# PCB_Switch.net
KiCad netlist of a schematic drawn in Altium Designer
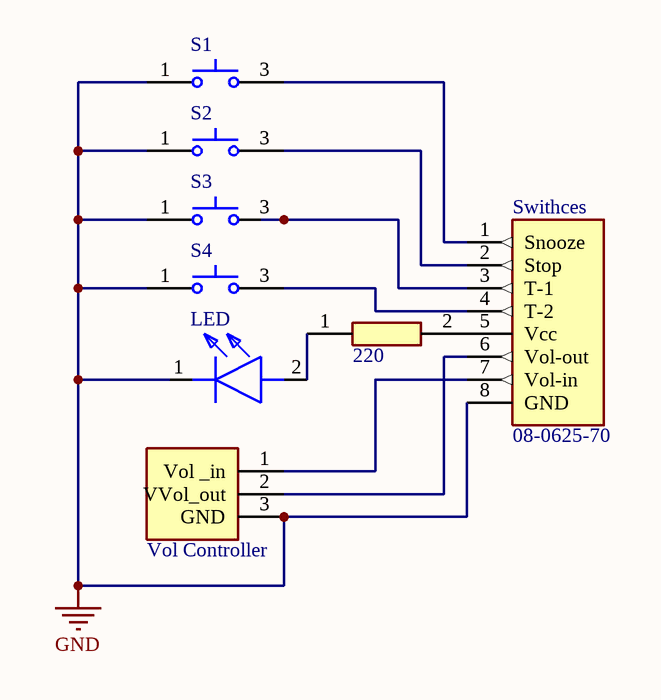
[diagram p0: PCB_Switch.SchDoc]

(export (version "E")
  (design (tool "Eeschema 10.0.6"))
  (components
    (comp (ref "LED")
      (value "SSL-LX5093TC")
      (footprint "SamacSys:SSL-LX5093SGC/B")
      (description "LED")
      (fields (field (name "MOUSER PART NUMBER") "696-SSL-LX5093TC"))
      (libsource (lib "*") (part "SSL-LX5093TC"))
    )
    (comp (ref "R")
      (value "220")
      (footprint "SamacSys:RESAD2400W59L1000D350")
      (description "Resistor")
      (fields (field (name "MANUFACTURER_PART_NUMBER") "293-220-RC"))
      (libsource (lib "*") (part "293-220-RC"))
    )
    (comp (ref "S1")
      (value "EP11SD1CBE")
      (footprint "SamacSys:EP11SD1CBE")
      (description "Switch (2-Pin Push)")
      (fields (field (name "MOUSER PART NUMBER") "611-EP11-003"))
      (libsource (lib "*") (part "EP11SD1CBE"))
    )
    (comp (ref "S2")
      (value "EP11SD1CBE")
      (footprint "SamacSys:EP11SD1CBE")
      (description "Switch (2-Pin Push)")
      (fields (field (name "MOUSER PART NUMBER") "611-EP11-003"))
      (libsource (lib "*") (part "EP11SD1CBE"))
    )
    (comp (ref "S3")
      (value "EP11SD1CBE")
      (footprint "SamacSys:EP11SD1CBE")
      (description "Switch (2-Pin Push)")
      (fields (field (name "MOUSER PART NUMBER") "611-EP11-003"))
      (libsource (lib "*") (part "EP11SD1CBE"))
    )
    (comp (ref "S4")
      (value "EP11SD1CBE")
      (footprint "SamacSys:EP11SD1CBE")
      (description "Switch (2-Pin Push)")
      (fields (field (name "MOUSER PART NUMBER") "611-EP11-003"))
      (libsource (lib "*") (part "EP11SD1CBE"))
    )
    (comp (ref "Swithces")
      (value "08-0625-70")
      (footprint "SamacSys:HDRV8W51P0X254_1X8_2032X254X816P")
      (description "Connector")
      (fields (field (name "MOUSER PART NUMBER") "535-08-0625-70"))
      (libsource (lib "*") (part "08-0625-70"))
    )
    (comp (ref "Vol Controller")
      (value "14910A0BHSX10502KA")
      (footprint "SamacSys:14910F0GJSX10103KA")
      (description "Variable Resistor")
      (fields (field (name "MOUSER PART NUMBER") "594-14910A0BHSP502KA"))
      (libsource (lib "*") (part "14910A0BHSX10502KA"))
    )
  )
  (nets
    (net (code "1") (name "GND") (class "Default")
      (node (ref "LED") (pin "1") (pinfunction "K_1") (pintype "passive"))
      (node (ref "S1") (pin "1") (pinfunction "NO_1_1") (pintype "passive"))
      (node (ref "S2") (pin "1") (pinfunction "NO_1_1") (pintype "passive"))
      (node (ref "S3") (pin "1") (pinfunction "NO_1_1") (pintype "passive"))
      (node (ref "S4") (pin "1") (pinfunction "NO_1_1") (pintype "passive"))
      (node (ref "Swithces") (pin "8") (pinfunction "GND_8") (pintype "power_in"))
      (node (ref "Vol Controller") (pin "3") (pinfunction "GND_3") (pintype "power_in"))
    )
    (net (code "2") (name "Net-(LED-A)") (class "Default")
      (node (ref "LED") (pin "2") (pinfunction "A_2") (pintype "passive"))
      (node (ref "R") (pin "1") (pinfunction "1_1") (pintype "passive"))
    )
    (net (code "3") (name "Net-(S1-NO_2)") (class "Default")
      (node (ref "S1") (pin "3") (pinfunction "NO_2_3") (pintype "passive"))
      (node (ref "Swithces") (pin "1") (pinfunction "Snooze_1") (pintype "output"))
    )
    (net (code "4") (name "Net-(S2-NO_2)") (class "Default")
      (node (ref "S2") (pin "3") (pinfunction "NO_2_3") (pintype "passive"))
      (node (ref "Swithces") (pin "2") (pinfunction "Stop_2") (pintype "output"))
    )
    (net (code "5") (name "Net-(S3-NO_2)") (class "Default")
      (node (ref "S3") (pin "3") (pinfunction "NO_2_3") (pintype "passive"))
      (node (ref "Swithces") (pin "3") (pinfunction "T-1_3") (pintype "output"))
    )
    (net (code "6") (name "Net-(S4-NO_2)") (class "Default")
      (node (ref "S4") (pin "3") (pinfunction "NO_2_3") (pintype "passive"))
      (node (ref "Swithces") (pin "4") (pinfunction "T-2_4") (pintype "output"))
    )
    (net (code "7") (name "Net-(Swithces-Vcc)") (class "Default")
      (node (ref "R") (pin "2") (pinfunction "2_2") (pintype "passive"))
      (node (ref "Swithces") (pin "5") (pinfunction "Vcc_5") (pintype "power_in"))
    )
    (net (code "8") (name "Net-(Swithces-Vol-in)") (class "Default")
      (node (ref "Swithces") (pin "7") (pinfunction "Vol-in_7") (pintype "output"))
      (node (ref "Vol Controller") (pin "1") (pinfunction "Vol__in_1") (pintype "passive"))
    )
    (net (code "9") (name "Net-(Swithces-Vol-out)") (class "Default")
      (node (ref "Swithces") (pin "6") (pinfunction "Vol-out_6") (pintype "output"))
      (node (ref "Vol Controller") (pin "2") (pinfunction "VVol_out_2") (pintype "passive"))
    )
  )
)
